# IRQF401RCT6.net
KiCad netlist of a schematic drawn in EAGLE
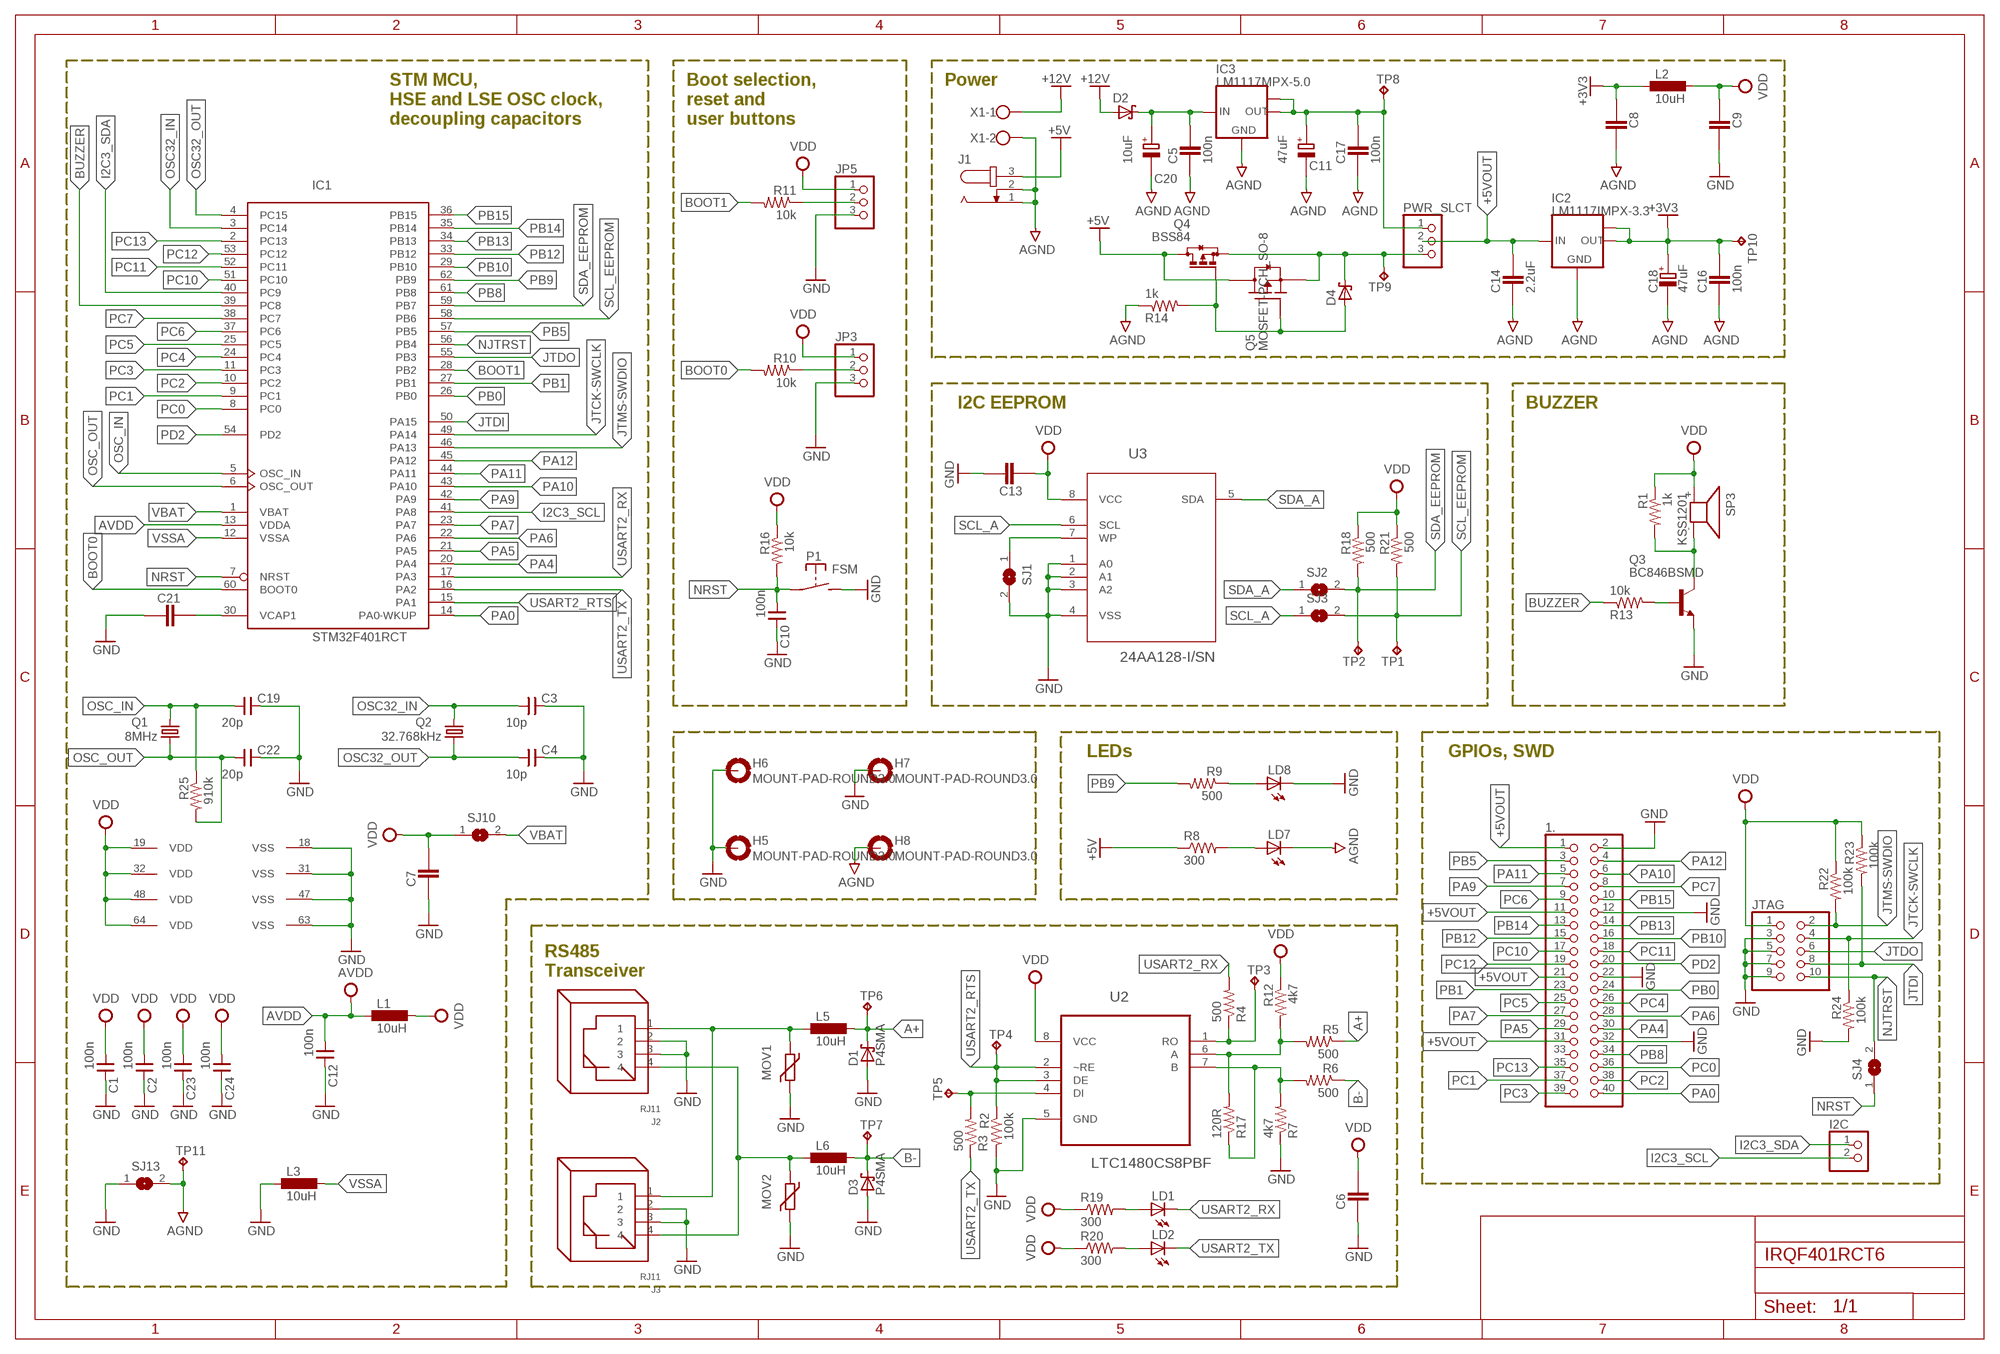
[diagram p0: schematic, sheet 1]

(export (version "E")
  (design (tool "Eeschema 10.0.6"))
  (components
    (comp (ref "1.")
      (value "PINHD-2X20")
      (footprint "eagle-import:2X20")
      (libsource (lib "eagle-import") (part "PINHD-2X20"))
    )
    (comp (ref "C1")
      (value "100n")
      (footprint "eagle-import:0805")
      (libsource (lib "eagle-import") (part "CNP-0805"))
    )
    (comp (ref "C2")
      (value "100n")
      (footprint "eagle-import:0805")
      (libsource (lib "eagle-import") (part "CNP-0805"))
    )
    (comp (ref "C3")
      (value "10p")
      (footprint "eagle-import:0805")
      (libsource (lib "eagle-import") (part "CNP-0805"))
    )
    (comp (ref "C4")
      (value "10p")
      (footprint "eagle-import:0805")
      (libsource (lib "eagle-import") (part "CNP-0805"))
    )
    (comp (ref "C5")
      (value "100n")
      (footprint "eagle-import:CAPC2012X145AN")
      (libsource (lib "eagle-import") (part "CAPACITOR_0805"))
    )
    (comp (ref "C6")
      (value "CAPACITOR_1206")
      (footprint "eagle-import:CAPC3215X168N")
      (libsource (lib "eagle-import") (part "CAPACITOR_1206"))
    )
    (comp (ref "C7")
      (value "CAPACITOR_1206")
      (footprint "eagle-import:CAPC3215X168N")
      (libsource (lib "eagle-import") (part "CAPACITOR_1206"))
    )
    (comp (ref "C8")
      (value "CAPACITOR_1206")
      (footprint "eagle-import:CAPC3215X168N")
      (libsource (lib "eagle-import") (part "CAPACITOR_1206"))
    )
    (comp (ref "C9")
      (value "CAPACITOR_1206")
      (footprint "eagle-import:CAPC3215X168N")
      (libsource (lib "eagle-import") (part "CAPACITOR_1206"))
    )
    (comp (ref "C10")
      (value "100n")
      (footprint "eagle-import:0805")
      (libsource (lib "eagle-import") (part "CNP-0805"))
    )
    (comp (ref "C11")
      (value "47uF")
      (footprint "eagle-import:CAPAE660X540N")
      (libsource (lib "eagle-import") (part "POLARISED_CASE_D"))
    )
    (comp (ref "C12")
      (value "100n")
      (footprint "eagle-import:0805")
      (libsource (lib "eagle-import") (part "CNP-0805"))
    )
    (comp (ref "C13")
      (value "CAPACITOR_1206")
      (footprint "eagle-import:CAPC3215X168N")
      (libsource (lib "eagle-import") (part "CAPACITOR_1206"))
    )
    (comp (ref "C14")
      (value "2.2uF")
      (footprint "eagle-import:CAPC3215X168N")
      (libsource (lib "eagle-import") (part "CAPACITOR_1206"))
    )
    (comp (ref "C16")
      (value "100n")
      (footprint "eagle-import:CAPC2012X145AN")
      (libsource (lib "eagle-import") (part "CAPACITOR_0805"))
    )
    (comp (ref "C17")
      (value "100n")
      (footprint "eagle-import:CAPC2012X145AN")
      (libsource (lib "eagle-import") (part "CAPACITOR_0805"))
    )
    (comp (ref "C18")
      (value "47uF")
      (footprint "eagle-import:CAPAE530X540N")
      (libsource (lib "eagle-import") (part "POLARISED_CASE_C"))
    )
    (comp (ref "C19")
      (value "20p")
      (footprint "eagle-import:0805")
      (libsource (lib "eagle-import") (part "CNP-0805"))
    )
    (comp (ref "C20")
      (value "10uF")
      (footprint "eagle-import:CAPAE430X540N")
      (libsource (lib "eagle-import") (part "POLARISED_CASE_B"))
    )
    (comp (ref "C21")
      (value "CAPACITOR_1206")
      (footprint "eagle-import:CAPC3215X168N")
      (libsource (lib "eagle-import") (part "CAPACITOR_1206"))
    )
    (comp (ref "C22")
      (value "20p")
      (footprint "eagle-import:0805")
      (libsource (lib "eagle-import") (part "CNP-0805"))
    )
    (comp (ref "C23")
      (value "100n")
      (footprint "eagle-import:0805")
      (libsource (lib "eagle-import") (part "CNP-0805"))
    )
    (comp (ref "C24")
      (value "100n")
      (footprint "eagle-import:0805")
      (libsource (lib "eagle-import") (part "CNP-0805"))
    )
    (comp (ref "D1")
      (value "P4SMA")
      (footprint "eagle-import:SMB")
      (libsource (lib "eagle-import") (part "SCHOTTKY-DIODESMD"))
    )
    (comp (ref "D2")
      (value "SCHOTTKY_SMA")
      (footprint "eagle-import:DIOM5326X292N")
      (libsource (lib "eagle-import") (part "SCHOTTKY_SMA"))
    )
    (comp (ref "D3")
      (value "P4SMA")
      (footprint "eagle-import:SMB")
      (libsource (lib "eagle-import") (part "SCHOTTKY-DIODESMD"))
    )
    (comp (ref "D4")
      (value "SCHOTTKY_SMA")
      (footprint "eagle-import:DIOM5326X292N")
      (libsource (lib "eagle-import") (part "SCHOTTKY_SMA"))
    )
    (comp (ref "H5")
      (value "MOUNT-PAD-ROUND3.0")
      (footprint "eagle-import:3,0-PAD")
      (libsource (lib "eagle-import") (part "MOUNT-PAD-ROUND3.0"))
    )
    (comp (ref "H6")
      (value "MOUNT-PAD-ROUND3.0")
      (footprint "eagle-import:3,0-PAD")
      (libsource (lib "eagle-import") (part "MOUNT-PAD-ROUND3.0"))
    )
    (comp (ref "H7")
      (value "MOUNT-PAD-ROUND3.0")
      (footprint "eagle-import:3,0-PAD")
      (libsource (lib "eagle-import") (part "MOUNT-PAD-ROUND3.0"))
    )
    (comp (ref "H8")
      (value "MOUNT-PAD-ROUND3.0")
      (footprint "eagle-import:3,0-PAD")
      (libsource (lib "eagle-import") (part "MOUNT-PAD-ROUND3.0"))
    )
    (comp (ref "I2C")
      (value "PINHD-1X2")
      (footprint "eagle-import:1X02")
      (libsource (lib "eagle-import") (part "PINHD-1X2"))
    )
    (comp (ref "IC1")
      (value "STM32F401RCT")
      (footprint "eagle-import:LQFP64")
      (libsource (lib "eagle-import") (part "STM32F401RTC"))
    )
    (comp (ref "IC2")
      (value "LM1117IMPX-3.3")
      (footprint "eagle-import:SOT223")
      (libsource (lib "eagle-import") (part "LM1117IMPX-3.3"))
    )
    (comp (ref "IC3")
      (value "LM1117MPX-5.0")
      (footprint "eagle-import:SOT223")
      (libsource (lib "eagle-import") (part "LM1117MPX-5.0"))
    )
    (comp (ref "J1")
      (value "JACK-PLUG1")
      (footprint "eagle-import:SPC4078")
      (libsource (lib "eagle-import") (part "JACK-PLUG1"))
    )
    (comp (ref "J2")
      (value "RJ11")
      (footprint "eagle-import:RJ11")
      (libsource (lib "eagle-import") (part "RJ11"))
    )
    (comp (ref "J3")
      (value "RJ11")
      (footprint "eagle-import:RJ11")
      (libsource (lib "eagle-import") (part "RJ11"))
    )
    (comp (ref "JP3")
      (value "PINHD-1X3")
      (footprint "eagle-import:1X03")
      (libsource (lib "eagle-import") (part "PINHD-1X3"))
    )
    (comp (ref "JP5")
      (value "PINHD-1X3")
      (footprint "eagle-import:1X03")
      (libsource (lib "eagle-import") (part "PINHD-1X3"))
    )
    (comp (ref "JTAG")
      (value "PINHD-2X5")
      (footprint "eagle-import:2X05")
      (libsource (lib "eagle-import") (part "PINHD-2X5"))
    )
    (comp (ref "L1")
      (value "10uH")
      (footprint "eagle-import:INDC1608X95N")
      (libsource (lib "eagle-import") (part "INDUCTOR_0603"))
    )
    (comp (ref "L2")
      (value "10uH")
      (footprint "eagle-import:INDC1608X95N")
      (libsource (lib "eagle-import") (part "INDUCTOR_0603"))
    )
    (comp (ref "L3")
      (value "10uH")
      (footprint "eagle-import:INDC1608X95N")
      (libsource (lib "eagle-import") (part "INDUCTOR_0603"))
    )
    (comp (ref "L5")
      (value "10uH")
      (footprint "eagle-import:INDC1608X95N")
      (libsource (lib "eagle-import") (part "INDUCTOR_0603"))
    )
    (comp (ref "L6")
      (value "10uH")
      (footprint "eagle-import:INDC1608X95N")
      (libsource (lib "eagle-import") (part "INDUCTOR_0603"))
    )
    (comp (ref "LD1")
      (value "LEDCHIPLED_0805")
      (footprint "eagle-import:CHIPLED_0805")
      (libsource (lib "eagle-import") (part "LEDCHIPLED_0805"))
    )
    (comp (ref "LD2")
      (value "LEDCHIPLED_0805")
      (footprint "eagle-import:CHIPLED_0805")
      (libsource (lib "eagle-import") (part "LEDCHIPLED_0805"))
    )
    (comp (ref "LD7")
      (value "LEDCHIPLED_0805")
      (footprint "eagle-import:CHIPLED_0805")
      (libsource (lib "eagle-import") (part "LEDCHIPLED_0805"))
    )
    (comp (ref "LD8")
      (value "LEDCHIPLED_0805")
      (footprint "eagle-import:CHIPLED_0805")
      (libsource (lib "eagle-import") (part "LEDCHIPLED_0805"))
    )
    (comp (ref "MOV1")
      (value "VARISTOR_0805")
      (footprint "eagle-import:VARC2012X70N")
      (libsource (lib "eagle-import") (part "VARISTOR_0805"))
    )
    (comp (ref "MOV2")
      (value "VARISTOR_0805")
      (footprint "eagle-import:VARC2012X70N")
      (libsource (lib "eagle-import") (part "VARISTOR_0805"))
    )
    (comp (ref "P1")
      (value "FSM")
      (footprint "eagle-import:FSM")
      (libsource (lib "eagle-import") (part "FSM"))
    )
    (comp (ref "PWR_SLCT")
      (value "PINHD-1X3")
      (footprint "eagle-import:1X03")
      (libsource (lib "eagle-import") (part "PINHD-1X3"))
    )
    (comp (ref "Q1")
      (value "8MHz")
      (footprint "eagle-import:HC49_S")
      (libsource (lib "eagle-import") (part "CRYTALHC49S"))
    )
    (comp (ref "Q2")
      (value "32.768kHz")
      (footprint "eagle-import:TC26H")
      (libsource (lib "eagle-import") (part "CRYTALTC26H"))
    )
    (comp (ref "Q3")
      (value "BC846BSMD")
      (footprint "eagle-import:SOT23")
      (libsource (lib "eagle-import") (part "BC846SMDB"))
    )
    (comp (ref "Q4")
      (value "BSS84")
      (footprint "eagle-import:SOT23")
      (libsource (lib "eagle-import") (part "BSS84"))
    )
    (comp (ref "Q5")
      (value "MOSFET-PCH_SO-8")
      (footprint "eagle-import:SOIC127P600X175-8AN")
      (libsource (lib "eagle-import") (part "MOSFET-PCH_SO-8"))
    )
    (comp (ref "R1")
      (value "1k")
      (footprint "eagle-import:M0805")
      (libsource (lib "eagle-import") (part "R-US_M0805"))
    )
    (comp (ref "R2")
      (value "100k")
      (footprint "eagle-import:M0805")
      (libsource (lib "eagle-import") (part "R-US_M0805"))
    )
    (comp (ref "R3")
      (value "500")
      (footprint "eagle-import:M0805")
      (libsource (lib "eagle-import") (part "R-US_M0805"))
    )
    (comp (ref "R4")
      (value "500")
      (footprint "eagle-import:M0805")
      (libsource (lib "eagle-import") (part "R-US_M0805"))
    )
    (comp (ref "R5")
      (value "500")
      (footprint "eagle-import:M0805")
      (libsource (lib "eagle-import") (part "R-US_M0805"))
    )
    (comp (ref "R6")
      (value "500")
      (footprint "eagle-import:M0805")
      (libsource (lib "eagle-import") (part "R-US_M0805"))
    )
    (comp (ref "R7")
      (value "4k7")
      (footprint "eagle-import:M0805")
      (libsource (lib "eagle-import") (part "R-US_M0805"))
    )
    (comp (ref "R8")
      (value "300")
      (footprint "eagle-import:M0805")
      (libsource (lib "eagle-import") (part "R-US_M0805"))
    )
    (comp (ref "R9")
      (value "500")
      (footprint "eagle-import:M0805")
      (libsource (lib "eagle-import") (part "R-US_M0805"))
    )
    (comp (ref "R10")
      (value "10k")
      (footprint "eagle-import:M0805")
      (libsource (lib "eagle-import") (part "R-US_M0805"))
    )
    (comp (ref "R11")
      (value "10k")
      (footprint "eagle-import:M0805")
      (libsource (lib "eagle-import") (part "R-US_M0805"))
    )
    (comp (ref "R12")
      (value "4k7")
      (footprint "eagle-import:M0805")
      (libsource (lib "eagle-import") (part "R-US_M0805"))
    )
    (comp (ref "R13")
      (value "10k")
      (footprint "eagle-import:M0805")
      (libsource (lib "eagle-import") (part "R-US_M0805"))
    )
    (comp (ref "R14")
      (value "1k")
      (footprint "eagle-import:M0805")
      (libsource (lib "eagle-import") (part "R-US_M0805"))
    )
    (comp (ref "R16")
      (value "10k")
      (footprint "eagle-import:M0805")
      (libsource (lib "eagle-import") (part "R-US_M0805"))
    )
    (comp (ref "R17")
      (value "120R")
      (footprint "eagle-import:M0805")
      (libsource (lib "eagle-import") (part "R-US_M0805"))
    )
    (comp (ref "R18")
      (value "500")
      (footprint "eagle-import:M0805")
      (libsource (lib "eagle-import") (part "R-US_M0805"))
    )
    (comp (ref "R19")
      (value "300")
      (footprint "eagle-import:M0805")
      (libsource (lib "eagle-import") (part "R-US_M0805"))
    )
    (comp (ref "R20")
      (value "300")
      (footprint "eagle-import:M0805")
      (libsource (lib "eagle-import") (part "R-US_M0805"))
    )
    (comp (ref "R21")
      (value "500")
      (footprint "eagle-import:M0805")
      (libsource (lib "eagle-import") (part "R-US_M0805"))
    )
    (comp (ref "R22")
      (value "100k")
      (footprint "eagle-import:M0805")
      (libsource (lib "eagle-import") (part "R-US_M0805"))
    )
    (comp (ref "R23")
      (value "100k")
      (footprint "eagle-import:M0805")
      (libsource (lib "eagle-import") (part "R-US_M0805"))
    )
    (comp (ref "R24")
      (value "100k")
      (footprint "eagle-import:M0805")
      (libsource (lib "eagle-import") (part "R-US_M0805"))
    )
    (comp (ref "R25")
      (value "910k")
      (footprint "eagle-import:M0805")
      (libsource (lib "eagle-import") (part "R-US_M0805"))
    )
    (comp (ref "SJ1") (value "SJ") (footprint "eagle-import:SJ") (libsource (lib "eagle-import") (part "SJ")))
    (comp (ref "SJ2") (value "SJ") (footprint "eagle-import:SJ") (libsource (lib "eagle-import") (part "SJ")))
    (comp (ref "SJ3") (value "SJ") (footprint "eagle-import:SJ") (libsource (lib "eagle-import") (part "SJ")))
    (comp (ref "SJ4") (value "SJ") (footprint "eagle-import:SJ") (libsource (lib "eagle-import") (part "SJ")))
    (comp (ref "SJ10")
      (value "SJ")
      (footprint "eagle-import:SJ")
      (libsource (lib "eagle-import") (part "SJ"))
    )
    (comp (ref "SJ13")
      (value "SJ")
      (footprint "eagle-import:SJ")
      (libsource (lib "eagle-import") (part "SJ"))
    )
    (comp (ref "SP3")
      (value "KSS1201")
      (footprint "eagle-import:KSS1201")
      (libsource (lib "eagle-import") (part "KSS1201"))
    )
    (comp (ref "TP1")
      (value "TPTP10R")
      (footprint "eagle-import:TP10R")
      (libsource (lib "eagle-import") (part "TPTP10R"))
    )
    (comp (ref "TP2")
      (value "TPTP10R")
      (footprint "eagle-import:TP10R")
      (libsource (lib "eagle-import") (part "TPTP10R"))
    )
    (comp (ref "TP3")
      (value "TPTP10R")
      (footprint "eagle-import:TP10R")
      (libsource (lib "eagle-import") (part "TPTP10R"))
    )
    (comp (ref "TP4")
      (value "TPTP10R")
      (footprint "eagle-import:TP10R")
      (libsource (lib "eagle-import") (part "TPTP10R"))
    )
    (comp (ref "TP5")
      (value "TPTP10R")
      (footprint "eagle-import:TP10R")
      (libsource (lib "eagle-import") (part "TPTP10R"))
    )
    (comp (ref "TP6")
      (value "TPTP10R")
      (footprint "eagle-import:TP10R")
      (libsource (lib "eagle-import") (part "TPTP10R"))
    )
    (comp (ref "TP7")
      (value "TPTP10R")
      (footprint "eagle-import:TP10R")
      (libsource (lib "eagle-import") (part "TPTP10R"))
    )
    (comp (ref "TP8")
      (value "TPTP10R")
      (footprint "eagle-import:TP10R")
      (libsource (lib "eagle-import") (part "TPTP10R"))
    )
    (comp (ref "TP9")
      (value "TPTP10R")
      (footprint "eagle-import:TP10R")
      (libsource (lib "eagle-import") (part "TPTP10R"))
    )
    (comp (ref "TP10")
      (value "TPTP10R")
      (footprint "eagle-import:TP10R")
      (libsource (lib "eagle-import") (part "TPTP10R"))
    )
    (comp (ref "TP11")
      (value "TPTP10R")
      (footprint "eagle-import:TP10R")
      (libsource (lib "eagle-import") (part "TPTP10R"))
    )
    (comp (ref "U2")
      (value "LTC1480CS8PBF")
      (footprint "eagle-import:SOIC127P600X175-8N")
      (fields (field (name "MPN") "LTC1480CS8#PBF"))
      (libsource (lib "eagle-import") (part "LTC1480CS8PBF"))
    )
    (comp (ref "U3")
      (value "24AA128-I/SN")
      (footprint "eagle-import:SOIC127P600X175-8N")
      (libsource (lib "eagle-import") (part "24AA128-I/SN"))
    )
    (comp (ref "X1")
      (value "W237-102")
      (footprint "eagle-import:W237-102")
      (libsource (lib "eagle-import") (part "W237-102"))
    )
  )
  (nets
    (net (code "1") (name "+3V3") (class "Default")
      (node (ref "C16") (pin "2") (pinfunction "2_2") (pintype "passive"))
      (node (ref "C18") (pin "+") (pinfunction "+_+") (pintype "passive"))
      (node (ref "C8") (pin "1") (pinfunction "1_1") (pintype "passive"))
      (node (ref "IC2") (pin "2") (pinfunction "OUT_2") (pintype "passive"))
      (node (ref "IC2") (pin "TAB") (pinfunction "OUT1_TAB") (pintype "passive"))
      (node (ref "L2") (pin "1") (pinfunction "1_1") (pintype "passive"))
      (node (ref "TP10") (pin "TP") (pinfunction "TP_TP") (pintype "input"))
    )
    (net (code "2") (name "+5V") (class "Default")
      (node (ref "J1") (pin "3") (pinfunction "3_3") (pintype "passive"))
      (node (ref "Q4") (pin "3") (pinfunction "D_3") (pintype "passive"))
      (node (ref "Q5") (pin "5") (pinfunction "D_5") (pintype "passive"))
      (node (ref "R8") (pin "1") (pinfunction "1_1") (pintype "passive"))
    )
    (net (code "3") (name "+5VOUT") (class "Default")
      (node (ref "1.") (pin "1") (pinfunction "1_1") (pintype "passive"))
      (node (ref "1.") (pin "11") (pinfunction "11_11") (pintype "passive"))
      (node (ref "1.") (pin "21") (pinfunction "21_21") (pintype "passive"))
      (node (ref "1.") (pin "31") (pinfunction "31_31") (pintype "passive"))
      (node (ref "C14") (pin "2") (pinfunction "2_2") (pintype "passive"))
      (node (ref "IC2") (pin "3") (pinfunction "IN_3") (pintype "input"))
      (node (ref "PWR_SLCT") (pin "2") (pinfunction "2_2") (pintype "passive"))
    )
    (net (code "4") (name "+12V") (class "Default")
      (node (ref "D2") (pin "A") (pinfunction "A_A") (pintype "passive"))
      (node (ref "X1") (pin "1") (pinfunction "KL_1") (pintype "passive"))
    )
    (net (code "5") (name "A+") (class "Default")
      (node (ref "D1") (pin "C") (pinfunction "C_C") (pintype "passive"))
      (node (ref "L5") (pin "2") (pinfunction "2_2") (pintype "passive"))
      (node (ref "R5") (pin "1") (pinfunction "1_1") (pintype "passive"))
      (node (ref "TP6") (pin "TP") (pinfunction "TP_TP") (pintype "input"))
    )
    (net (code "6") (name "AGND") (class "Default")
      (node (ref "C11") (pin "-") (pinfunction "-_-") (pintype "passive"))
      (node (ref "C14") (pin "1") (pinfunction "1_1") (pintype "passive"))
      (node (ref "C16") (pin "1") (pinfunction "1_1") (pintype "passive"))
      (node (ref "C17") (pin "1") (pinfunction "1_1") (pintype "passive"))
      (node (ref "C18") (pin "-") (pinfunction "-_-") (pintype "passive"))
      (node (ref "C20") (pin "-") (pinfunction "-_-") (pintype "passive"))
      (node (ref "C5") (pin "1") (pinfunction "1_1") (pintype "passive"))
      (node (ref "C8") (pin "2") (pinfunction "2_2") (pintype "passive"))
      (node (ref "H8") (pin "B3,0") (pinfunction "MOUNT_B3,0") (pintype "passive"))
      (node (ref "IC2") (pin "1") (pinfunction "GND_1") (pintype "input"))
      (node (ref "IC3") (pin "1") (pinfunction "GND_1") (pintype "input"))
      (node (ref "J1") (pin "1") (pinfunction "1_1") (pintype "passive"))
      (node (ref "J1") (pin "2") (pinfunction "2_2") (pintype "passive"))
      (node (ref "LD7") (pin "C") (pinfunction "C_C") (pintype "passive"))
      (node (ref "R14") (pin "1") (pinfunction "1_1") (pintype "passive"))
      (node (ref "SJ13") (pin "2") (pinfunction "2_2") (pintype "passive"))
      (node (ref "TP11") (pin "TP") (pinfunction "TP_TP") (pintype "input"))
      (node (ref "X1") (pin "2") (pinfunction "KL_2") (pintype "passive"))
    )
    (net (code "7") (name "AVDD") (class "Default")
      (node (ref "C12") (pin "1") (pinfunction "1_1") (pintype "passive"))
      (node (ref "IC1") (pin "13") (pinfunction "VDDA_13") (pintype "power_in"))
      (node (ref "L1") (pin "1") (pinfunction "1_1") (pintype "passive"))
    )
    (net (code "8") (name "B-") (class "Default")
      (node (ref "D3") (pin "C") (pinfunction "C_C") (pintype "passive"))
      (node (ref "L6") (pin "2") (pinfunction "2_2") (pintype "passive"))
      (node (ref "R6") (pin "1") (pinfunction "1_1") (pintype "passive"))
      (node (ref "TP7") (pin "TP") (pinfunction "TP_TP") (pintype "input"))
    )
    (net (code "9") (name "BOOT0") (class "Default")
      (node (ref "IC1") (pin "60") (pinfunction "BOOT0_60") (pintype "input"))
      (node (ref "R10") (pin "2") (pinfunction "2_2") (pintype "passive"))
    )
    (net (code "10") (name "BOOT1") (class "Default")
      (node (ref "IC1") (pin "28") (pinfunction "PB2_28") (pintype "bidirectional"))
      (node (ref "R11") (pin "2") (pinfunction "2_2") (pintype "passive"))
    )
    (net (code "11") (name "BUZZER") (class "Default")
      (node (ref "IC1") (pin "39") (pinfunction "PC8_39") (pintype "bidirectional"))
      (node (ref "R13") (pin "1") (pinfunction "1_1") (pintype "passive"))
    )
    (net (code "12") (name "GND") (class "Default")
      (node (ref "1.") (pin "12") (pinfunction "12_12") (pintype "passive"))
      (node (ref "1.") (pin "2") (pinfunction "2_2") (pintype "passive"))
      (node (ref "1.") (pin "22") (pinfunction "22_22") (pintype "passive"))
      (node (ref "1.") (pin "32") (pinfunction "32_32") (pintype "passive"))
      (node (ref "C1") (pin "2") (pinfunction "2_2") (pintype "passive"))
      (node (ref "C10") (pin "2") (pinfunction "2_2") (pintype "passive"))
      (node (ref "C12") (pin "2") (pinfunction "2_2") (pintype "passive"))
      (node (ref "C13") (pin "2") (pinfunction "2_2") (pintype "passive"))
      (node (ref "C19") (pin "2") (pinfunction "2_2") (pintype "passive"))
      (node (ref "C2") (pin "2") (pinfunction "2_2") (pintype "passive"))
      (node (ref "C21") (pin "1") (pinfunction "1_1") (pintype "passive"))
      (node (ref "C22") (pin "2") (pinfunction "2_2") (pintype "passive"))
      (node (ref "C23") (pin "2") (pinfunction "2_2") (pintype "passive"))
      (node (ref "C24") (pin "2") (pinfunction "2_2") (pintype "passive"))
      (node (ref "C3") (pin "2") (pinfunction "2_2") (pintype "passive"))
      (node (ref "C4") (pin "2") (pinfunction "2_2") (pintype "passive"))
      (node (ref "C6") (pin "1") (pinfunction "1_1") (pintype "passive"))
      (node (ref "C7") (pin "1") (pinfunction "1_1") (pintype "passive"))
      (node (ref "C9") (pin "2") (pinfunction "2_2") (pintype "passive"))
      (node (ref "D1") (pin "A") (pinfunction "A_A") (pintype "passive"))
      (node (ref "D3") (pin "A") (pinfunction "A_A") (pintype "passive"))
      (node (ref "H5") (pin "B3,0") (pinfunction "MOUNT_B3,0") (pintype "passive"))
      (node (ref "H6") (pin "B3,0") (pinfunction "MOUNT_B3,0") (pintype "passive"))
      (node (ref "H7") (pin "B3,0") (pinfunction "MOUNT_B3,0") (pintype "passive"))
      (node (ref "IC1") (pin "18") (pinfunction "VSS_18") (pintype "power_in"))
      (node (ref "IC1") (pin "31") (pinfunction "VSS_31") (pintype "power_in"))
      (node (ref "IC1") (pin "47") (pinfunction "VSS_47") (pintype "power_in"))
      (node (ref "IC1") (pin "63") (pinfunction "VSS_63") (pintype "power_in"))
      (node (ref "J2") (pin "2") (pinfunction "2_2") (pintype "bidirectional"))
      (node (ref "J2") (pin "3") (pinfunction "3_3") (pintype "bidirectional"))
      (node (ref "J3") (pin "2") (pinfunction "2_2") (pintype "bidirectional"))
      (node (ref "J3") (pin "3") (pinfunction "3_3") (pintype "bidirectional"))
      (node (ref "JP3") (pin "3") (pinfunction "3_3") (pintype "passive"))
      (node (ref "JP5") (pin "3") (pinfunction "3_3") (pintype "passive"))
      (node (ref "JTAG") (pin "3") (pinfunction "3_3") (pintype "passive"))
      (node (ref "JTAG") (pin "5") (pinfunction "5_5") (pintype "passive"))
      (node (ref "JTAG") (pin "7") (pinfunction "7_7") (pintype "passive"))
      (node (ref "JTAG") (pin "9") (pinfunction "9_9") (pintype "passive"))
      (node (ref "L3") (pin "1") (pinfunction "1_1") (pintype "passive"))
      (node (ref "LD8") (pin "C") (pinfunction "C_C") (pintype "passive"))
      (node (ref "MOV1") (pin "1") (pinfunction "1_1") (pintype "passive"))
      (node (ref "MOV2") (pin "1") (pinfunction "1_1") (pintype "passive"))
      (node (ref "P1") (pin "P$2") (pinfunction "S_P$2") (pintype "passive"))
      (node (ref "Q3") (pin "2") (pinfunction "E_2") (pintype "passive"))
      (node (ref "R2") (pin "2") (pinfunction "2_2") (pintype "passive"))
      (node (ref "R24") (pin "2") (pinfunction "2_2") (pintype "passive"))
      (node (ref "R7") (pin "1") (pinfunction "1_1") (pintype "passive"))
      (node (ref "SJ1") (pin "2") (pinfunction "2_2") (pintype "passive"))
      (node (ref "SJ13") (pin "1") (pinfunction "1_1") (pintype "passive"))
      (node (ref "U2") (pin "5") (pinfunction "GND_5") (pintype "passive"))
      (node (ref "U3") (pin "1") (pinfunction "A0_1") (pintype "input"))
      (node (ref "U3") (pin "2") (pinfunction "A1_2") (pintype "input"))
      (node (ref "U3") (pin "3") (pinfunction "A2_3") (pintype "input"))
      (node (ref "U3") (pin "4") (pinfunction "VSS_4") (pintype "power_in"))
    )
    (net (code "13") (name "I2C3_SCL") (class "Default")
      (node (ref "I2C") (pin "2") (pinfunction "2_2") (pintype "passive"))
      (node (ref "IC1") (pin "41") (pinfunction "PA8_41") (pintype "bidirectional"))
    )
    (net (code "14") (name "I2C3_SDA") (class "Default")
      (node (ref "I2C") (pin "1") (pinfunction "1_1") (pintype "passive"))
      (node (ref "IC1") (pin "40") (pinfunction "PC9_40") (pintype "bidirectional"))
    )
    (net (code "15") (name "JTCK-SWCLK") (class "Default")
      (node (ref "IC1") (pin "49") (pinfunction "PA14_49") (pintype "bidirectional"))
      (node (ref "JTAG") (pin "4") (pinfunction "4_4") (pintype "passive"))
      (node (ref "R24") (pin "1") (pinfunction "1_1") (pintype "passive"))
    )
    (net (code "16") (name "JTDI") (class "Default")
      (node (ref "IC1") (pin "50") (pinfunction "PA15_50") (pintype "bidirectional"))
      (node (ref "JTAG") (pin "8") (pinfunction "8_8") (pintype "passive"))
      (node (ref "R23") (pin "2") (pinfunction "2_2") (pintype "passive"))
    )
    (net (code "17") (name "JTDO") (class "Default")
      (node (ref "IC1") (pin "55") (pinfunction "PB3_55") (pintype "bidirectional"))
      (node (ref "JTAG") (pin "6") (pinfunction "6_6") (pintype "passive"))
    )
    (net (code "18") (name "JTMS-SWDIO") (class "Default")
      (node (ref "IC1") (pin "46") (pinfunction "PA13_46") (pintype "bidirectional"))
      (node (ref "JTAG") (pin "2") (pinfunction "2_2") (pintype "passive"))
      (node (ref "R22") (pin "2") (pinfunction "2_2") (pintype "passive"))
    )
    (net (code "19") (name "NJTRST") (class "Default")
      (node (ref "IC1") (pin "56") (pinfunction "PB4_56") (pintype "bidirectional"))
      (node (ref "JTAG") (pin "10") (pinfunction "10_10") (pintype "passive"))
      (node (ref "SJ4") (pin "2") (pinfunction "2_2") (pintype "passive"))
    )
    (net (code "20") (name "NRST") (class "Default")
      (node (ref "C10") (pin "1") (pinfunction "1_1") (pintype "passive"))
      (node (ref "IC1") (pin "7") (pinfunction "NRST_7") (pintype "bidirectional"))
      (node (ref "P1") (pin "P$1") (pinfunction "P_P$1") (pintype "passive"))
      (node (ref "R16") (pin "2") (pinfunction "2_2") (pintype "passive"))
      (node (ref "SJ4") (pin "1") (pinfunction "1_1") (pintype "passive"))
    )
    (net (code "21") (name "Net-(IC1A-VCAP1)") (class "Default")
      (node (ref "C21") (pin "2") (pinfunction "2_2") (pintype "passive"))
      (node (ref "IC1") (pin "30") (pinfunction "VCAP1_30") (pintype "power_in"))
    )
    (net (code "22") (name "Net-(IC3-IN)") (class "Default")
      (node (ref "C20") (pin "+") (pinfunction "+_+") (pintype "passive"))
      (node (ref "C5") (pin "2") (pinfunction "2_2") (pintype "passive"))
      (node (ref "D2") (pin "K") (pinfunction "K_K") (pintype "passive"))
      (node (ref "IC3") (pin "3") (pinfunction "IN_3") (pintype "input"))
    )
    (net (code "23") (name "Net-(IC3-OUT)") (class "Default")
      (node (ref "C11") (pin "+") (pinfunction "+_+") (pintype "passive"))
      (node (ref "C17") (pin "2") (pinfunction "2_2") (pintype "passive"))
      (node (ref "IC3") (pin "2") (pinfunction "OUT_2") (pintype "passive"))
      (node (ref "IC3") (pin "TAB") (pinfunction "OUT1_TAB") (pintype "passive"))
      (node (ref "PWR_SLCT") (pin "1") (pinfunction "1_1") (pintype "passive"))
      (node (ref "TP8") (pin "TP") (pinfunction "TP_TP") (pintype "input"))
    )
    (net (code "24") (name "Net-(J2-Pad1)") (class "Default")
      (node (ref "J2") (pin "1") (pinfunction "1_1") (pintype "bidirectional"))
      (node (ref "J3") (pin "1") (pinfunction "1_1") (pintype "bidirectional"))
      (node (ref "L5") (pin "1") (pinfunction "1_1") (pintype "passive"))
      (node (ref "MOV1") (pin "2") (pinfunction "2_2") (pintype "passive"))
    )
    (net (code "25") (name "Net-(J2-Pad4)") (class "Default")
      (node (ref "J2") (pin "4") (pinfunction "4_4") (pintype "bidirectional"))
      (node (ref "J3") (pin "4") (pinfunction "4_4") (pintype "bidirectional"))
      (node (ref "L6") (pin "1") (pinfunction "1_1") (pintype "passive"))
      (node (ref "MOV2") (pin "2") (pinfunction "2_2") (pintype "passive"))
    )
    (net (code "26") (name "Net-(JP3-Pad2)") (class "Default")
      (node (ref "JP3") (pin "2") (pinfunction "2_2") (pintype "passive"))
      (node (ref "R10") (pin "1") (pinfunction "1_1") (pintype "passive"))
    )
    (net (code "27") (name "Net-(JP5-Pad2)") (class "Default")
      (node (ref "JP5") (pin "2") (pinfunction "2_2") (pintype "passive"))
      (node (ref "R11") (pin "1") (pinfunction "1_1") (pintype "passive"))
    )
    (net (code "28") (name "Net-(LD1-PadA)") (class "Default")
      (node (ref "LD1") (pin "A") (pinfunction "A_A") (pintype "passive"))
      (node (ref "R19") (pin "2") (pinfunction "2_2") (pintype "passive"))
    )
    (net (code "29") (name "Net-(LD2-PadA)") (class "Default")
      (node (ref "LD2") (pin "A") (pinfunction "A_A") (pintype "passive"))
      (node (ref "R20") (pin "2") (pinfunction "2_2") (pintype "passive"))
    )
    (net (code "30") (name "Net-(LD7-PadA)") (class "Default")
      (node (ref "LD7") (pin "A") (pinfunction "A_A") (pintype "passive"))
      (node (ref "R8") (pin "2") (pinfunction "2_2") (pintype "passive"))
    )
    (net (code "31") (name "Net-(LD8-PadA)") (class "Default")
      (node (ref "LD8") (pin "A") (pinfunction "A_A") (pintype "passive"))
      (node (ref "R9") (pin "1") (pinfunction "1_1") (pintype "passive"))
    )
    (net (code "32") (name "Net-(Q3-B)") (class "Default")
      (node (ref "Q3") (pin "1") (pinfunction "B_1") (pintype "passive"))
      (node (ref "R13") (pin "2") (pinfunction "2_2") (pintype "passive"))
    )
    (net (code "33") (name "Net-(Q3-C)") (class "Default")
      (node (ref "Q3") (pin "3") (pinfunction "C_3") (pintype "passive"))
      (node (ref "R1") (pin "2") (pinfunction "2_2") (pintype "passive"))
      (node (ref "SP3") (pin "-") (pinfunction "2_-") (pintype "passive"))
    )
    (net (code "34") (name "Net-(Q4-G)") (class "Default")
      (node (ref "D4") (pin "A") (pinfunction "A_A") (pintype "passive"))
      (node (ref "Q4") (pin "1") (pinfunction "G_1") (pintype "passive"))
      (node (ref "Q5") (pin "4") (pinfunction "G_4") (pintype "passive"))
      (node (ref "R14") (pin "2") (pinfunction "2_2") (pintype "passive"))
    )
    (net (code "35") (name "Net-(Q4-S)") (class "Default")
      (node (ref "D4") (pin "K") (pinfunction "K_K") (pintype "passive"))
      (node (ref "PWR_SLCT") (pin "3") (pinfunction "3_3") (pintype "passive"))
      (node (ref "Q4") (pin "2") (pinfunction "S_2") (pintype "passive"))
      (node (ref "Q5") (pin "1") (pinfunction "S_1") (pintype "passive"))
      (node (ref "TP9") (pin "TP") (pinfunction "TP_TP") (pintype "input"))
    )
    (net (code "36") (name "Net-(U2-A)") (class "Default")
      (node (ref "R12") (pin "2") (pinfunction "2_2") (pintype "passive"))
      (node (ref "R17") (pin "2") (pinfunction "2_2") (pintype "passive"))
      (node (ref "R5") (pin "2") (pinfunction "2_2") (pintype "passive"))
      (node (ref "U2") (pin "6") (pinfunction "A_6") (pintype "bidirectional"))
    )
    (net (code "37") (name "Net-(U2-B)") (class "Default")
      (node (ref "R17") (pin "1") (pinfunction "1_1") (pintype "passive"))
      (node (ref "R6") (pin "2") (pinfunction "2_2") (pintype "passive"))
      (node (ref "R7") (pin "2") (pinfunction "2_2") (pintype "passive"))
      (node (ref "U2") (pin "7") (pinfunction "B_7") (pintype "bidirectional"))
    )
    (net (code "38") (name "Net-(U2-DI)") (class "Default")
      (node (ref "R3") (pin "2") (pinfunction "2_2") (pintype "passive"))
      (node (ref "TP5") (pin "TP") (pinfunction "TP_TP") (pintype "input"))
      (node (ref "U2") (pin "4") (pinfunction "DI_4") (pintype "input"))
    )
    (net (code "39") (name "Net-(U2-RO)") (class "Default")
      (node (ref "R4") (pin "1") (pinfunction "1_1") (pintype "passive"))
      (node (ref "TP3") (pin "TP") (pinfunction "TP_TP") (pintype "input"))
      (node (ref "U2") (pin "1") (pinfunction "RO_1") (pintype "output"))
    )
    (net (code "40") (name "Net-(U3-WP)") (class "Default")
      (node (ref "SJ1") (pin "1") (pinfunction "1_1") (pintype "passive"))
      (node (ref "U3") (pin "7") (pinfunction "WP_7") (pintype "input"))
    )
    (net (code "41") (name "OSC32_IN") (class "Default")
      (node (ref "C3") (pin "1") (pinfunction "1_1") (pintype "passive"))
      (node (ref "IC1") (pin "3") (pinfunction "PC14_3") (pintype "bidirectional"))
      (node (ref "Q2") (pin "2") (pinfunction "2_2") (pintype "passive"))
    )
    (net (code "42") (name "OSC32_OUT") (class "Default")
      (node (ref "C4") (pin "1") (pinfunction "1_1") (pintype "passive"))
      (node (ref "IC1") (pin "4") (pinfunction "PC15_4") (pintype "bidirectional"))
      (node (ref "Q2") (pin "1") (pinfunction "1_1") (pintype "passive"))
    )
    (net (code "43") (name "OSC_IN") (class "Default")
      (node (ref "C19") (pin "1") (pinfunction "1_1") (pintype "passive"))
      (node (ref "IC1") (pin "5") (pinfunction "OSC_IN_5") (pintype "bidirectional"))
      (node (ref "Q1") (pin "2") (pinfunction "2_2") (pintype "passive"))
      (node (ref "R25") (pin "1") (pinfunction "1_1") (pintype "passive"))
    )
    (net (code "44") (name "OSC_OUT") (class "Default")
      (node (ref "C22") (pin "1") (pinfunction "1_1") (pintype "passive"))
      (node (ref "IC1") (pin "6") (pinfunction "OSC_OUT_6") (pintype "bidirectional"))
      (node (ref "Q1") (pin "1") (pinfunction "1_1") (pintype "passive"))
      (node (ref "R25") (pin "2") (pinfunction "2_2") (pintype "passive"))
    )
    (net (code "45") (name "PA0") (class "Default")
      (node (ref "1.") (pin "40") (pinfunction "40_40") (pintype "passive"))
      (node (ref "IC1") (pin "14") (pinfunction "PA0-WKUP_14") (pintype "bidirectional"))
    )
    (net (code "46") (name "PA4") (class "Default")
      (node (ref "1.") (pin "30") (pinfunction "30_30") (pintype "passive"))
      (node (ref "IC1") (pin "20") (pinfunction "PA4_20") (pintype "bidirectional"))
    )
    (net (code "47") (name "PA5") (class "Default")
      (node (ref "1.") (pin "29") (pinfunction "29_29") (pintype "passive"))
      (node (ref "IC1") (pin "21") (pinfunction "PA5_21") (pintype "bidirectional"))
    )
    (net (code "48") (name "PA6") (class "Default")
      (node (ref "1.") (pin "28") (pinfunction "28_28") (pintype "passive"))
      (node (ref "IC1") (pin "22") (pinfunction "PA6_22") (pintype "bidirectional"))
    )
    (net (code "49") (name "PA7") (class "Default")
      (node (ref "1.") (pin "27") (pinfunction "27_27") (pintype "passive"))
      (node (ref "IC1") (pin "23") (pinfunction "PA7_23") (pintype "bidirectional"))
    )
    (net (code "50") (name "PA9") (class "Default")
      (node (ref "1.") (pin "7") (pinfunction "7_7") (pintype "passive"))
      (node (ref "IC1") (pin "42") (pinfunction "PA9_42") (pintype "bidirectional"))
    )
    (net (code "51") (name "PA10") (class "Default")
      (node (ref "1.") (pin "6") (pinfunction "6_6") (pintype "passive"))
      (node (ref "IC1") (pin "43") (pinfunction "PA10_43") (pintype "bidirectional"))
    )
    (net (code "52") (name "PA11") (class "Default")
      (node (ref "1.") (pin "5") (pinfunction "5_5") (pintype "passive"))
      (node (ref "IC1") (pin "44") (pinfunction "PA11_44") (pintype "bidirectional"))
    )
    (net (code "53") (name "PA12") (class "Default")
      (node (ref "1.") (pin "4") (pinfunction "4_4") (pintype "passive"))
      (node (ref "IC1") (pin "45") (pinfunction "PA12_45") (pintype "bidirectional"))
    )
    (net (code "54") (name "PB0") (class "Default")
      (node (ref "1.") (pin "24") (pinfunction "24_24") (pintype "passive"))
      (node (ref "IC1") (pin "26") (pinfunction "PB0_26") (pintype "bidirectional"))
    )
    (net (code "55") (name "PB1") (class "Default")
      (node (ref "1.") (pin "23") (pinfunction "23_23") (pintype "passive"))
      (node (ref "IC1") (pin "27") (pinfunction "PB1_27") (pintype "bidirectional"))
    )
    (net (code "56") (name "PB5") (class "Default")
      (node (ref "1.") (pin "3") (pinfunction "3_3") (pintype "passive"))
      (node (ref "IC1") (pin "57") (pinfunction "PB5_57") (pintype "bidirectional"))
    )
    (net (code "57") (name "PB8") (class "Default")
      (node (ref "1.") (pin "34") (pinfunction "34_34") (pintype "passive"))
      (node (ref "IC1") (pin "61") (pinfunction "PB8_61") (pintype "bidirectional"))
    )
    (net (code "58") (name "PB9") (class "Default")
      (node (ref "IC1") (pin "62") (pinfunction "PB9_62") (pintype "bidirectional"))
      (node (ref "R9") (pin "2") (pinfunction "2_2") (pintype "passive"))
    )
    (net (code "59") (name "PB10") (class "Default")
      (node (ref "1.") (pin "16") (pinfunction "16_16") (pintype "passive"))
      (node (ref "IC1") (pin "29") (pinfunction "PB10_29") (pintype "bidirectional"))
    )
    (net (code "60") (name "PB12") (class "Default")
      (node (ref "1.") (pin "15") (pinfunction "15_15") (pintype "passive"))
      (node (ref "IC1") (pin "33") (pinfunction "PB12_33") (pintype "bidirectional"))
    )
    (net (code "61") (name "PB13") (class "Default")
      (node (ref "1.") (pin "14") (pinfunction "14_14") (pintype "passive"))
      (node (ref "IC1") (pin "34") (pinfunction "PB13_34") (pintype "bidirectional"))
    )
    (net (code "62") (name "PB14") (class "Default")
      (node (ref "1.") (pin "13") (pinfunction "13_13") (pintype "passive"))
      (node (ref "IC1") (pin "35") (pinfunction "PB14_35") (pintype "bidirectional"))
    )
    (net (code "63") (name "PB15") (class "Default")
      (node (ref "1.") (pin "10") (pinfunction "10_10") (pintype "passive"))
      (node (ref "IC1") (pin "36") (pinfunction "PB15_36") (pintype "bidirectional"))
    )
    (net (code "64") (name "PC0") (class "Default")
      (node (ref "1.") (pin "36") (pinfunction "36_36") (pintype "passive"))
      (node (ref "IC1") (pin "8") (pinfunction "PC0_8") (pintype "bidirectional"))
    )
    (net (code "65") (name "PC1") (class "Default")
      (node (ref "1.") (pin "37") (pinfunction "37_37") (pintype "passive"))
      (node (ref "IC1") (pin "9") (pinfunction "PC1_9") (pintype "bidirectional"))
    )
    (net (code "66") (name "PC2") (class "Default")
      (node (ref "1.") (pin "38") (pinfunction "38_38") (pintype "passive"))
      (node (ref "IC1") (pin "10") (pinfunction "PC2_10") (pintype "bidirectional"))
    )
    (net (code "67") (name "PC3") (class "Default")
      (node (ref "1.") (pin "39") (pinfunction "39_39") (pintype "passive"))
      (node (ref "IC1") (pin "11") (pinfunction "PC3_11") (pintype "bidirectional"))
    )
    (net (code "68") (name "PC4") (class "Default")
      (node (ref "1.") (pin "26") (pinfunction "26_26") (pintype "passive"))
      (node (ref "IC1") (pin "24") (pinfunction "PC4_24") (pintype "bidirectional"))
    )
    (net (code "69") (name "PC5") (class "Default")
      (node (ref "1.") (pin "25") (pinfunction "25_25") (pintype "passive"))
      (node (ref "IC1") (pin "25") (pinfunction "PC5_25") (pintype "bidirectional"))
    )
    (net (code "70") (name "PC6") (class "Default")
      (node (ref "1.") (pin "9") (pinfunction "9_9") (pintype "passive"))
      (node (ref "IC1") (pin "37") (pinfunction "PC6_37") (pintype "bidirectional"))
    )
    (net (code "71") (name "PC7") (class "Default")
      (node (ref "1.") (pin "8") (pinfunction "8_8") (pintype "passive"))
      (node (ref "IC1") (pin "38") (pinfunction "PC7_38") (pintype "bidirectional"))
    )
    (net (code "72") (name "PC10") (class "Default")
      (node (ref "1.") (pin "17") (pinfunction "17_17") (pintype "passive"))
      (node (ref "IC1") (pin "51") (pinfunction "PC10_51") (pintype "bidirectional"))
    )
    (net (code "73") (name "PC11") (class "Default")
      (node (ref "1.") (pin "18") (pinfunction "18_18") (pintype "passive"))
      (node (ref "IC1") (pin "52") (pinfunction "PC11_52") (pintype "bidirectional"))
    )
    (net (code "74") (name "PC12") (class "Default")
      (node (ref "1.") (pin "19") (pinfunction "19_19") (pintype "passive"))
      (node (ref "IC1") (pin "53") (pinfunction "PC12_53") (pintype "bidirectional"))
    )
    (net (code "75") (name "PC13") (class "Default")
      (node (ref "1.") (pin "35") (pinfunction "35_35") (pintype "passive"))
      (node (ref "IC1") (pin "2") (pinfunction "PC13_2") (pintype "bidirectional"))
    )
    (net (code "76") (name "PD2") (class "Default")
      (node (ref "1.") (pin "20") (pinfunction "20_20") (pintype "passive"))
      (node (ref "IC1") (pin "54") (pinfunction "PD2_54") (pintype "bidirectional"))
    )
    (net (code "77") (name "SCL_A") (class "Default")
      (node (ref "SJ3") (pin "1") (pinfunction "1_1") (pintype "passive"))
      (node (ref "U3") (pin "6") (pinfunction "SCL_6") (pintype "input"))
    )
    (net (code "78") (name "SCL_EEPROM") (class "Default")
      (node (ref "IC1") (pin "58") (pinfunction "PB6_58") (pintype "bidirectional"))
      (node (ref "R21") (pin "2") (pinfunction "2_2") (pintype "passive"))
      (node (ref "SJ3") (pin "2") (pinfunction "2_2") (pintype "passive"))
      (node (ref "TP1") (pin "TP") (pinfunction "TP_TP") (pintype "input"))
    )
    (net (code "79") (name "SDA_A") (class "Default")
      (node (ref "SJ2") (pin "1") (pinfunction "1_1") (pintype "passive"))
      (node (ref "U3") (pin "5") (pinfunction "SDA_5") (pintype "bidirectional"))
    )
    (net (code "80") (name "SDA_EEPROM") (class "Default")
      (node (ref "IC1") (pin "59") (pinfunction "PB7_59") (pintype "bidirectional"))
      (node (ref "R18") (pin "2") (pinfunction "2_2") (pintype "passive"))
      (node (ref "SJ2") (pin "2") (pinfunction "2_2") (pintype "passive"))
      (node (ref "TP2") (pin "TP") (pinfunction "TP_TP") (pintype "input"))
    )
    (net (code "81") (name "USART2_RTS") (class "Default")
      (node (ref "IC1") (pin "15") (pinfunction "PA1_15") (pintype "bidirectional"))
      (node (ref "R2") (pin "1") (pinfunction "1_1") (pintype "passive"))
      (node (ref "TP4") (pin "TP") (pinfunction "TP_TP") (pintype "input"))
      (node (ref "U2") (pin "2") (pinfunction "~{RE}_2") (pintype "input"))
      (node (ref "U2") (pin "3") (pinfunction "DE_3") (pintype "input"))
    )
    (net (code "82") (name "USART2_RX") (class "Default")
      (node (ref "IC1") (pin "17") (pinfunction "PA3_17") (pintype "bidirectional"))
      (node (ref "LD1") (pin "C") (pinfunction "C_C") (pintype "passive"))
      (node (ref "R4") (pin "2") (pinfunction "2_2") (pintype "passive"))
    )
    (net (code "83") (name "USART2_TX") (class "Default")
      (node (ref "IC1") (pin "16") (pinfunction "PA2_16") (pintype "bidirectional"))
      (node (ref "LD2") (pin "C") (pinfunction "C_C") (pintype "passive"))
      (node (ref "R3") (pin "1") (pinfunction "1_1") (pintype "passive"))
    )
    (net (code "84") (name "VBAT") (class "Default")
      (node (ref "IC1") (pin "1") (pinfunction "VBAT_1") (pintype "power_in"))
      (node (ref "SJ10") (pin "2") (pinfunction "2_2") (pintype "passive"))
    )
    (net (code "85") (name "VDD") (class "Default")
      (node (ref "C1") (pin "1") (pinfunction "1_1") (pintype "passive"))
      (node (ref "C13") (pin "1") (pinfunction "1_1") (pintype "passive"))
      (node (ref "C2") (pin "1") (pinfunction "1_1") (pintype "passive"))
      (node (ref "C23") (pin "1") (pinfunction "1_1") (pintype "passive"))
      (node (ref "C24") (pin "1") (pinfunction "1_1") (pintype "passive"))
      (node (ref "C6") (pin "2") (pinfunction "2_2") (pintype "passive"))
      (node (ref "C7") (pin "2") (pinfunction "2_2") (pintype "passive"))
      (node (ref "C9") (pin "1") (pinfunction "1_1") (pintype "passive"))
      (node (ref "IC1") (pin "19") (pinfunction "VDD_19") (pintype "power_in"))
      (node (ref "IC1") (pin "32") (pinfunction "VDD_32") (pintype "power_in"))
      (node (ref "IC1") (pin "48") (pinfunction "VDD_48") (pintype "power_in"))
      (node (ref "IC1") (pin "64") (pinfunction "VDD_64") (pintype "power_in"))
      (node (ref "JP3") (pin "1") (pinfunction "1_1") (pintype "passive"))
      (node (ref "JP5") (pin "1") (pinfunction "1_1") (pintype "passive"))
      (node (ref "JTAG") (pin "1") (pinfunction "1_1") (pintype "passive"))
      (node (ref "L1") (pin "2") (pinfunction "2_2") (pintype "passive"))
      (node (ref "L2") (pin "2") (pinfunction "2_2") (pintype "passive"))
      (node (ref "R1") (pin "1") (pinfunction "1_1") (pintype "passive"))
      (node (ref "R12") (pin "1") (pinfunction "1_1") (pintype "passive"))
      (node (ref "R16") (pin "1") (pinfunction "1_1") (pintype "passive"))
      (node (ref "R18") (pin "1") (pinfunction "1_1") (pintype "passive"))
      (node (ref "R19") (pin "1") (pinfunction "1_1") (pintype "passive"))
      (node (ref "R20") (pin "1") (pinfunction "1_1") (pintype "passive"))
      (node (ref "R21") (pin "1") (pinfunction "1_1") (pintype "passive"))
      (node (ref "R22") (pin "1") (pinfunction "1_1") (pintype "passive"))
      (node (ref "R23") (pin "1") (pinfunction "1_1") (pintype "passive"))
      (node (ref "SJ10") (pin "1") (pinfunction "1_1") (pintype "passive"))
      (node (ref "SP3") (pin "+") (pinfunction "1_+") (pintype "passive"))
      (node (ref "U2") (pin "8") (pinfunction "VCC_8") (pintype "power_in"))
      (node (ref "U3") (pin "8") (pinfunction "VCC_8") (pintype "power_in"))
    )
    (net (code "86") (name "VSSA") (class "Default")
      (node (ref "IC1") (pin "12") (pinfunction "VSSA_12") (pintype "power_in"))
      (node (ref "L3") (pin "2") (pinfunction "2_2") (pintype "passive"))
    )
    (net (code "87") (name "unconnected-(1.-Pad33)") (class "Default")
      (node (ref "1.") (pin "33") (pinfunction "33_33") (pintype "passive"))
    )
  )
)
